# output_cpld.net
KiCad netlist of a schematic drawn in EAGLE
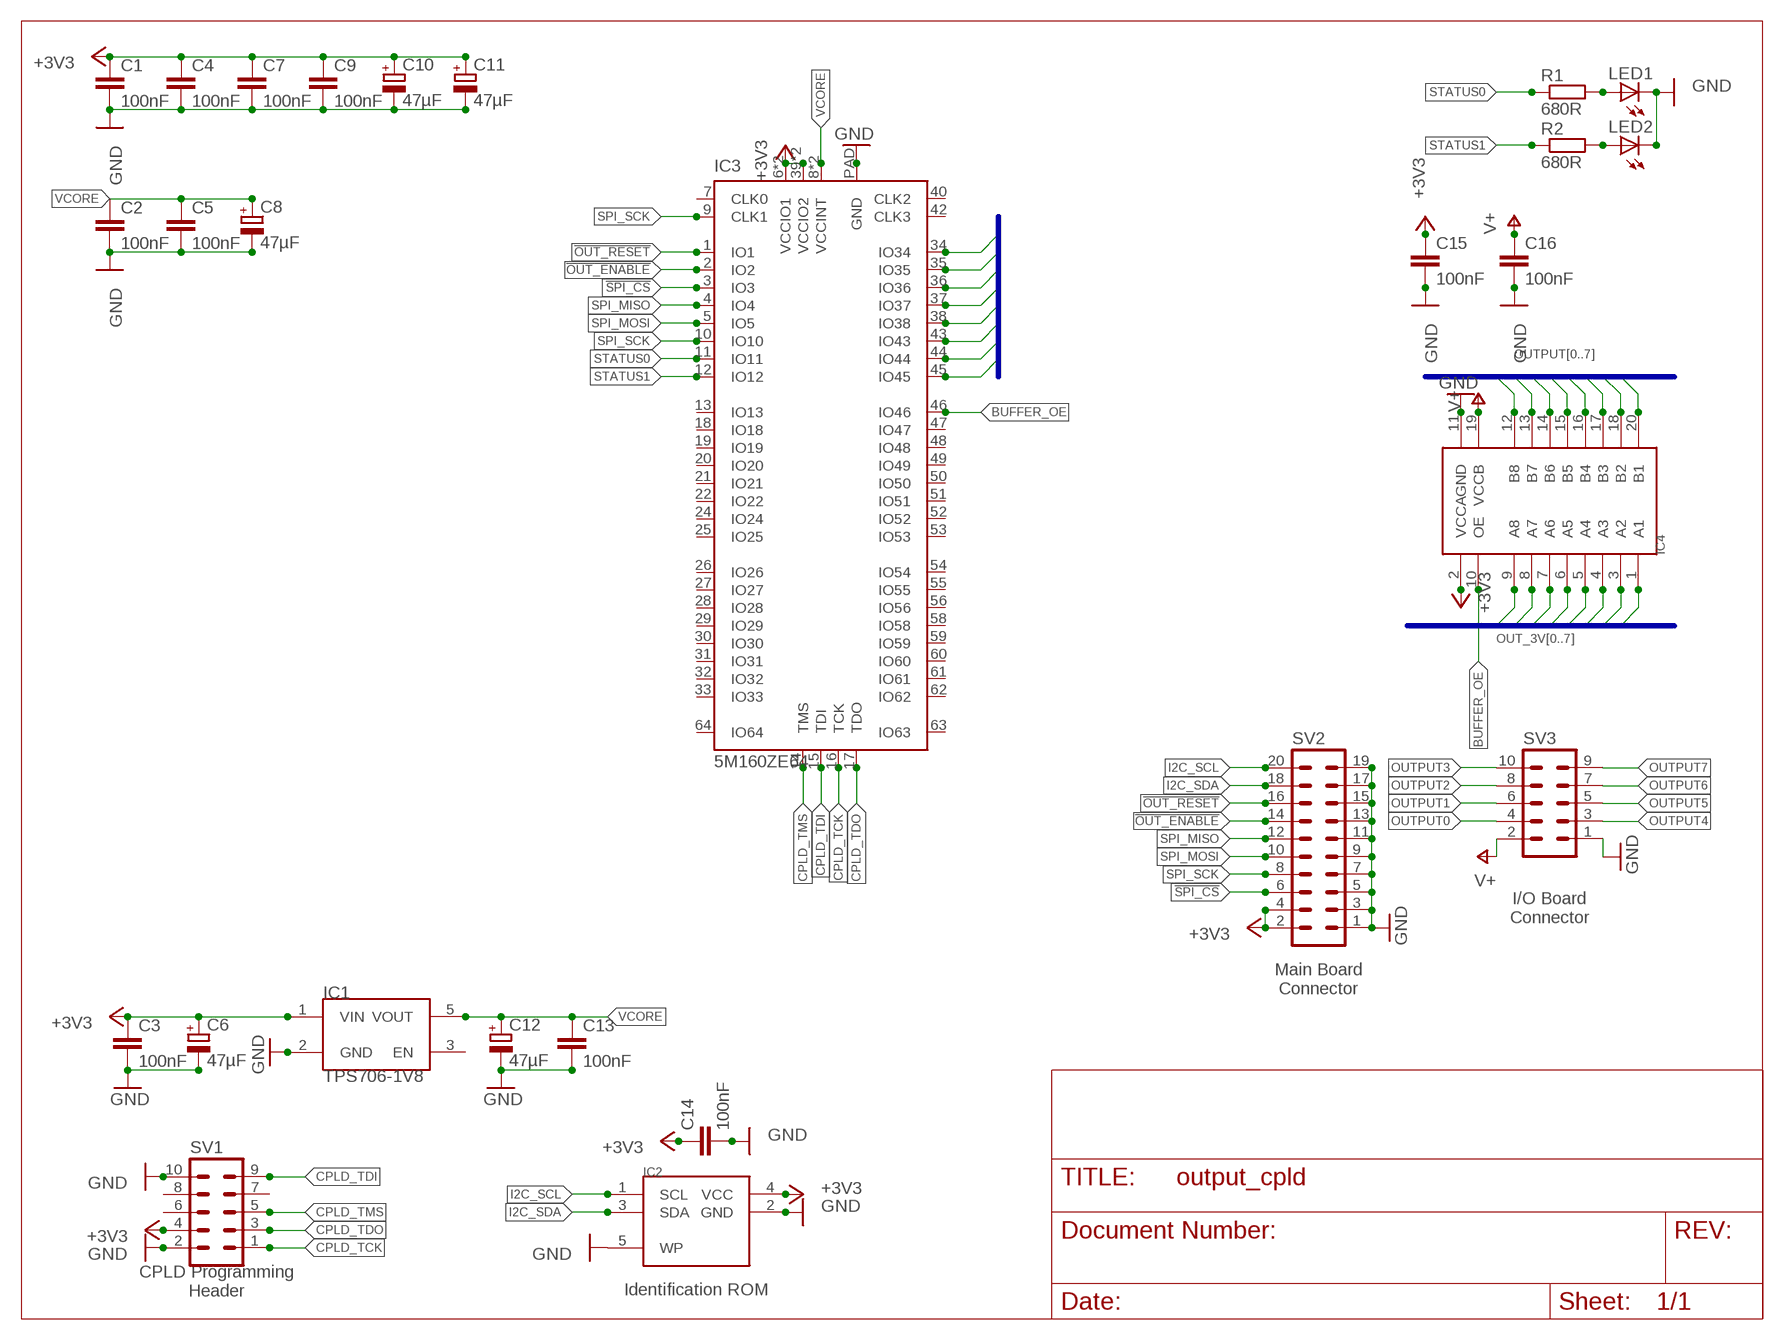
[diagram p0: schematic, sheet 1]

(export (version "E")
  (design (tool "Eeschema 10.0.6"))
  (components
    (comp (ref "C1")
      (value "100nF")
      (footprint "eagle-import:C0805")
      (libsource (lib "eagle-import") (part "C-EUC0805"))
    )
    (comp (ref "C2")
      (value "100nF")
      (footprint "eagle-import:C0805")
      (libsource (lib "eagle-import") (part "C-EUC0805"))
    )
    (comp (ref "C3")
      (value "100nF")
      (footprint "eagle-import:C0805")
      (libsource (lib "eagle-import") (part "C-EUC0805"))
    )
    (comp (ref "C4")
      (value "100nF")
      (footprint "eagle-import:C0805")
      (libsource (lib "eagle-import") (part "C-EUC0805"))
    )
    (comp (ref "C5")
      (value "100nF")
      (footprint "eagle-import:C0805")
      (libsource (lib "eagle-import") (part "C-EUC0805"))
    )
    (comp (ref "C6")
      (value "47µF")
      (footprint "eagle-import:CT6032")
      (libsource (lib "eagle-import") (part "CPOL-EUCT6032"))
    )
    (comp (ref "C7")
      (value "100nF")
      (footprint "eagle-import:C0805")
      (libsource (lib "eagle-import") (part "C-EUC0805"))
    )
    (comp (ref "C8")
      (value "47µF")
      (footprint "eagle-import:CT6032")
      (libsource (lib "eagle-import") (part "CPOL-EUCT6032"))
    )
    (comp (ref "C9")
      (value "100nF")
      (footprint "eagle-import:C0805")
      (libsource (lib "eagle-import") (part "C-EUC0805"))
    )
    (comp (ref "C10")
      (value "47µF")
      (footprint "eagle-import:CT6032")
      (libsource (lib "eagle-import") (part "CPOL-EUCT6032"))
    )
    (comp (ref "C11")
      (value "47µF")
      (footprint "eagle-import:CT6032")
      (libsource (lib "eagle-import") (part "CPOL-EUCT6032"))
    )
    (comp (ref "C12")
      (value "47µF")
      (footprint "eagle-import:CT6032")
      (libsource (lib "eagle-import") (part "CPOL-EUCT6032"))
    )
    (comp (ref "C13")
      (value "100nF")
      (footprint "eagle-import:C0805")
      (libsource (lib "eagle-import") (part "C-EUC0805"))
    )
    (comp (ref "C14")
      (value "100nF")
      (footprint "eagle-import:C0805")
      (libsource (lib "eagle-import") (part "C-EUC0805"))
    )
    (comp (ref "C15")
      (value "100nF")
      (footprint "eagle-import:C0805")
      (libsource (lib "eagle-import") (part "C-EUC0805"))
    )
    (comp (ref "C16")
      (value "100nF")
      (footprint "eagle-import:C0805")
      (libsource (lib "eagle-import") (part "C-EUC0805"))
    )
    (comp (ref "IC1")
      (value "TPS706-1V8")
      (footprint "eagle-import:SOT23-5")
      (libsource (lib "eagle-import") (part "TPS706SOT23-5"))
    )
    (comp (ref "IC2")
      (value "AT24C02D")
      (footprint "eagle-import:SOT23-5")
      (libsource (lib "eagle-import") (part "AT24C02D"))
    )
    (comp (ref "IC3")
      (value "5M160ZE64")
      (footprint "eagle-import:EQFP64")
      (libsource (lib "eagle-import") (part "5M160ZE64"))
    )
    (comp (ref "IC4")
      (value "TXB0108TSSOP20")
      (footprint "eagle-import:TSSOP20")
      (libsource (lib "eagle-import") (part "TXB0108TSSOP20"))
    )
    (comp (ref "LED1")
      (value "LEDCHIPLED_1206")
      (footprint "eagle-import:CHIPLED_1206")
      (libsource (lib "eagle-import") (part "LEDCHIPLED_1206"))
    )
    (comp (ref "LED2")
      (value "LEDCHIPLED_1206")
      (footprint "eagle-import:CHIPLED_1206")
      (libsource (lib "eagle-import") (part "LEDCHIPLED_1206"))
    )
    (comp (ref "R1")
      (value "680R")
      (footprint "eagle-import:M0805")
      (libsource (lib "eagle-import") (part "R-EU_M0805"))
    )
    (comp (ref "R2")
      (value "680R")
      (footprint "eagle-import:M0805")
      (libsource (lib "eagle-import") (part "R-EU_M0805"))
    )
    (comp (ref "SV1")
      (value "MA05-2")
      (footprint "eagle-import:MA05-2")
      (libsource (lib "eagle-import") (part "MA05-2"))
    )
    (comp (ref "SV2")
      (value "MA10-2")
      (footprint "eagle-import:MA10-2")
      (libsource (lib "eagle-import") (part "MA10-2"))
    )
    (comp (ref "SV3")
      (value "MA05-2")
      (footprint "eagle-import:MA05-2")
      (libsource (lib "eagle-import") (part "MA05-2"))
    )
  )
  (nets
    (net (code "1") (name "+3V3") (class "Default")
      (node (ref "C1") (pin "1") (pinfunction "1_1") (pintype "passive"))
      (node (ref "C10") (pin "+") (pinfunction "+_+") (pintype "passive"))
      (node (ref "C11") (pin "+") (pinfunction "+_+") (pintype "passive"))
      (node (ref "C14") (pin "1") (pinfunction "1_1") (pintype "passive"))
      (node (ref "C15") (pin "1") (pinfunction "1_1") (pintype "passive"))
      (node (ref "C3") (pin "1") (pinfunction "1_1") (pintype "passive"))
      (node (ref "C4") (pin "1") (pinfunction "1_1") (pintype "passive"))
      (node (ref "C6") (pin "+") (pinfunction "+_+") (pintype "passive"))
      (node (ref "C7") (pin "1") (pinfunction "1_1") (pintype "passive"))
      (node (ref "C9") (pin "1") (pinfunction "1_1") (pintype "passive"))
      (node (ref "IC1") (pin "1") (pinfunction "VIN_1") (pintype "bidirectional"))
      (node (ref "IC2") (pin "4") (pinfunction "VCC_4") (pintype "power_in"))
      (node (ref "IC3") (pin "23") (pinfunction "VCCIO1_23") (pintype "power_in"))
      (node (ref "IC3") (pin "39") (pinfunction "VCCIO2_39") (pintype "power_in"))
      (node (ref "IC3") (pin "57") (pinfunction "VCCIO2_57") (pintype "power_in"))
      (node (ref "IC3") (pin "6") (pinfunction "VCCIO1_6") (pintype "power_in"))
      (node (ref "IC4") (pin "2") (pinfunction "VCCA_2") (pintype "bidirectional"))
      (node (ref "SV1") (pin "4") (pinfunction "4_4") (pintype "passive"))
      (node (ref "SV2") (pin "2") (pinfunction "2_2") (pintype "passive"))
      (node (ref "SV2") (pin "4") (pinfunction "4_4") (pintype "passive"))
    )
    (net (code "3") (name "/OUT_3V0") (class "Default")
      (node (ref "IC3") (pin "34") (pinfunction "IO34_34") (pintype "bidirectional"))
      (node (ref "IC4") (pin "1") (pinfunction "A1_1") (pintype "bidirectional"))
    )
    (net (code "4") (name "/OUT_3V1") (class "Default")
      (node (ref "IC3") (pin "35") (pinfunction "IO35_35") (pintype "bidirectional"))
      (node (ref "IC4") (pin "3") (pinfunction "A2_3") (pintype "bidirectional"))
    )
    (net (code "5") (name "/OUT_3V2") (class "Default")
      (node (ref "IC3") (pin "36") (pinfunction "IO36_36") (pintype "bidirectional"))
      (node (ref "IC4") (pin "4") (pinfunction "A3_4") (pintype "bidirectional"))
    )
    (net (code "6") (name "/OUT_3V3") (class "Default")
      (node (ref "IC3") (pin "37") (pinfunction "IO37_37") (pintype "bidirectional"))
      (node (ref "IC4") (pin "5") (pinfunction "A4_5") (pintype "bidirectional"))
    )
    (net (code "7") (name "/OUT_3V4") (class "Default")
      (node (ref "IC3") (pin "38") (pinfunction "IO38_38") (pintype "bidirectional"))
      (node (ref "IC4") (pin "6") (pinfunction "A5_6") (pintype "bidirectional"))
    )
    (net (code "8") (name "/OUT_3V5") (class "Default")
      (node (ref "IC3") (pin "43") (pinfunction "IO43_43") (pintype "bidirectional"))
      (node (ref "IC4") (pin "7") (pinfunction "A6_7") (pintype "bidirectional"))
    )
    (net (code "9") (name "/OUT_3V6") (class "Default")
      (node (ref "IC3") (pin "44") (pinfunction "IO44_44") (pintype "bidirectional"))
      (node (ref "IC4") (pin "8") (pinfunction "A7_8") (pintype "bidirectional"))
    )
    (net (code "10") (name "/OUT_3V7") (class "Default")
      (node (ref "IC3") (pin "45") (pinfunction "IO45_45") (pintype "bidirectional"))
      (node (ref "IC4") (pin "9") (pinfunction "A8_9") (pintype "bidirectional"))
    )
    (net (code "12") (name "/~{OUT_ENABLE}") (class "Default")
      (node (ref "IC3") (pin "2") (pinfunction "IO2_2") (pintype "bidirectional"))
      (node (ref "SV2") (pin "14") (pinfunction "14_14") (pintype "passive"))
    )
    (net (code "13") (name "/~{OUT_RESET}") (class "Default")
      (node (ref "IC3") (pin "1") (pinfunction "IO1_1") (pintype "bidirectional"))
      (node (ref "SV2") (pin "16") (pinfunction "16_16") (pintype "passive"))
    )
    (net (code "14") (name "/~{SPI_CS}") (class "Default")
      (node (ref "IC3") (pin "3") (pinfunction "IO3_3") (pintype "bidirectional"))
      (node (ref "SV2") (pin "6") (pinfunction "6_6") (pintype "passive"))
    )
    (net (code "15") (name "BUFFER_OE") (class "Default")
      (node (ref "IC3") (pin "46") (pinfunction "IO46_46") (pintype "bidirectional"))
      (node (ref "IC4") (pin "10") (pinfunction "OE_10") (pintype "bidirectional"))
    )
    (net (code "16") (name "CPLD_TCK") (class "Default")
      (node (ref "IC3") (pin "16") (pinfunction "TCK_16") (pintype "input"))
      (node (ref "SV1") (pin "1") (pinfunction "1_1") (pintype "passive"))
    )
    (net (code "17") (name "CPLD_TDI") (class "Default")
      (node (ref "IC3") (pin "15") (pinfunction "TDI_15") (pintype "input"))
      (node (ref "SV1") (pin "9") (pinfunction "9_9") (pintype "passive"))
    )
    (net (code "18") (name "CPLD_TDO") (class "Default")
      (node (ref "IC3") (pin "17") (pinfunction "TDO_17") (pintype "output"))
      (node (ref "SV1") (pin "3") (pinfunction "3_3") (pintype "passive"))
    )
    (net (code "19") (name "CPLD_TMS") (class "Default")
      (node (ref "IC3") (pin "14") (pinfunction "TMS_14") (pintype "input"))
      (node (ref "SV1") (pin "5") (pinfunction "5_5") (pintype "passive"))
    )
    (net (code "20") (name "GND") (class "Default")
      (node (ref "C1") (pin "2") (pinfunction "2_2") (pintype "passive"))
      (node (ref "C10") (pin "-") (pinfunction "-_-") (pintype "passive"))
      (node (ref "C11") (pin "-") (pinfunction "-_-") (pintype "passive"))
      (node (ref "C12") (pin "-") (pinfunction "-_-") (pintype "passive"))
      (node (ref "C13") (pin "2") (pinfunction "2_2") (pintype "passive"))
      (node (ref "C14") (pin "2") (pinfunction "2_2") (pintype "passive"))
      (node (ref "C15") (pin "2") (pinfunction "2_2") (pintype "passive"))
      (node (ref "C16") (pin "2") (pinfunction "2_2") (pintype "passive"))
      (node (ref "C2") (pin "2") (pinfunction "2_2") (pintype "passive"))
      (node (ref "C3") (pin "2") (pinfunction "2_2") (pintype "passive"))
      (node (ref "C4") (pin "2") (pinfunction "2_2") (pintype "passive"))
      (node (ref "C5") (pin "2") (pinfunction "2_2") (pintype "passive"))
      (node (ref "C6") (pin "-") (pinfunction "-_-") (pintype "passive"))
      (node (ref "C7") (pin "2") (pinfunction "2_2") (pintype "passive"))
      (node (ref "C8") (pin "-") (pinfunction "-_-") (pintype "passive"))
      (node (ref "C9") (pin "2") (pinfunction "2_2") (pintype "passive"))
      (node (ref "IC1") (pin "2") (pinfunction "GND_2") (pintype "bidirectional"))
      (node (ref "IC2") (pin "2") (pinfunction "GND_2") (pintype "power_in"))
      (node (ref "IC2") (pin "5") (pinfunction "WP_5") (pintype "bidirectional"))
      (node (ref "IC3") (pin "PAD") (pinfunction "GND_PAD") (pintype "power_in"))
      (node (ref "IC4") (pin "11") (pinfunction "GND_11") (pintype "bidirectional"))
      (node (ref "LED1") (pin "C") (pinfunction "C_C") (pintype "passive"))
      (node (ref "LED2") (pin "C") (pinfunction "C_C") (pintype "passive"))
      (node (ref "SV1") (pin "10") (pinfunction "10_10") (pintype "passive"))
      (node (ref "SV1") (pin "2") (pinfunction "2_2") (pintype "passive"))
      (node (ref "SV2") (pin "1") (pinfunction "1_1") (pintype "passive"))
      (node (ref "SV2") (pin "11") (pinfunction "11_11") (pintype "passive"))
      (node (ref "SV2") (pin "13") (pinfunction "13_13") (pintype "passive"))
      (node (ref "SV2") (pin "15") (pinfunction "15_15") (pintype "passive"))
      (node (ref "SV2") (pin "17") (pinfunction "17_17") (pintype "passive"))
      (node (ref "SV2") (pin "19") (pinfunction "19_19") (pintype "passive"))
      (node (ref "SV2") (pin "3") (pinfunction "3_3") (pintype "passive"))
      (node (ref "SV2") (pin "5") (pinfunction "5_5") (pintype "passive"))
      (node (ref "SV2") (pin "7") (pinfunction "7_7") (pintype "passive"))
      (node (ref "SV2") (pin "9") (pinfunction "9_9") (pintype "passive"))
      (node (ref "SV3") (pin "1") (pinfunction "1_1") (pintype "passive"))
    )
    (net (code "21") (name "I2C_SCL") (class "Default")
      (node (ref "IC2") (pin "1") (pinfunction "SCL_1") (pintype "bidirectional"))
      (node (ref "SV2") (pin "20") (pinfunction "20_20") (pintype "passive"))
    )
    (net (code "22") (name "I2C_SDA") (class "Default")
      (node (ref "IC2") (pin "3") (pinfunction "SDA_3") (pintype "bidirectional"))
      (node (ref "SV2") (pin "18") (pinfunction "18_18") (pintype "passive"))
    )
    (net (code "23") (name "Net-(LED1-PadA)") (class "Default")
      (node (ref "LED1") (pin "A") (pinfunction "A_A") (pintype "passive"))
      (node (ref "R1") (pin "2") (pinfunction "2_2") (pintype "passive"))
    )
    (net (code "24") (name "Net-(LED2-PadA)") (class "Default")
      (node (ref "LED2") (pin "A") (pinfunction "A_A") (pintype "passive"))
      (node (ref "R2") (pin "2") (pinfunction "2_2") (pintype "passive"))
    )
    (net (code "25") (name "OUTPUT0") (class "Default")
      (node (ref "IC4") (pin "20") (pinfunction "B1_20") (pintype "bidirectional"))
      (node (ref "SV3") (pin "4") (pinfunction "4_4") (pintype "passive"))
    )
    (net (code "26") (name "OUTPUT1") (class "Default")
      (node (ref "IC4") (pin "18") (pinfunction "B2_18") (pintype "bidirectional"))
      (node (ref "SV3") (pin "6") (pinfunction "6_6") (pintype "passive"))
    )
    (net (code "27") (name "OUTPUT2") (class "Default")
      (node (ref "IC4") (pin "17") (pinfunction "B3_17") (pintype "bidirectional"))
      (node (ref "SV3") (pin "8") (pinfunction "8_8") (pintype "passive"))
    )
    (net (code "28") (name "OUTPUT3") (class "Default")
      (node (ref "IC4") (pin "16") (pinfunction "B4_16") (pintype "bidirectional"))
      (node (ref "SV3") (pin "10") (pinfunction "10_10") (pintype "passive"))
    )
    (net (code "29") (name "OUTPUT4") (class "Default")
      (node (ref "IC4") (pin "15") (pinfunction "B5_15") (pintype "bidirectional"))
      (node (ref "SV3") (pin "3") (pinfunction "3_3") (pintype "passive"))
    )
    (net (code "30") (name "OUTPUT5") (class "Default")
      (node (ref "IC4") (pin "14") (pinfunction "B6_14") (pintype "bidirectional"))
      (node (ref "SV3") (pin "5") (pinfunction "5_5") (pintype "passive"))
    )
    (net (code "31") (name "OUTPUT6") (class "Default")
      (node (ref "IC4") (pin "13") (pinfunction "B7_13") (pintype "bidirectional"))
      (node (ref "SV3") (pin "7") (pinfunction "7_7") (pintype "passive"))
    )
    (net (code "32") (name "OUTPUT7") (class "Default")
      (node (ref "IC4") (pin "12") (pinfunction "B8_12") (pintype "bidirectional"))
      (node (ref "SV3") (pin "9") (pinfunction "9_9") (pintype "passive"))
    )
    (net (code "33") (name "SPI_MISO") (class "Default")
      (node (ref "IC3") (pin "4") (pinfunction "IO4_4") (pintype "bidirectional"))
      (node (ref "SV2") (pin "12") (pinfunction "12_12") (pintype "passive"))
    )
    (net (code "34") (name "SPI_MOSI") (class "Default")
      (node (ref "IC3") (pin "5") (pinfunction "IO5_5") (pintype "bidirectional"))
      (node (ref "SV2") (pin "10") (pinfunction "10_10") (pintype "passive"))
    )
    (net (code "35") (name "SPI_SCK") (class "Default")
      (node (ref "IC3") (pin "10") (pinfunction "IO10_10") (pintype "bidirectional"))
      (node (ref "IC3") (pin "9") (pinfunction "CLK1_9") (pintype "bidirectional"))
      (node (ref "SV2") (pin "8") (pinfunction "8_8") (pintype "passive"))
    )
    (net (code "36") (name "STATUS0") (class "Default")
      (node (ref "IC3") (pin "11") (pinfunction "IO11_11") (pintype "bidirectional"))
      (node (ref "R1") (pin "1") (pinfunction "1_1") (pintype "passive"))
    )
    (net (code "37") (name "STATUS1") (class "Default")
      (node (ref "IC3") (pin "12") (pinfunction "IO12_12") (pintype "bidirectional"))
      (node (ref "R2") (pin "1") (pinfunction "1_1") (pintype "passive"))
    )
    (net (code "38") (name "V+") (class "Default")
      (node (ref "C16") (pin "1") (pinfunction "1_1") (pintype "passive"))
      (node (ref "IC4") (pin "19") (pinfunction "VCCB_19") (pintype "bidirectional"))
      (node (ref "SV3") (pin "2") (pinfunction "2_2") (pintype "passive"))
    )
    (net (code "39") (name "VCORE") (class "Default")
      (node (ref "C12") (pin "+") (pinfunction "+_+") (pintype "passive"))
      (node (ref "C13") (pin "1") (pinfunction "1_1") (pintype "passive"))
      (node (ref "C2") (pin "1") (pinfunction "1_1") (pintype "passive"))
      (node (ref "C5") (pin "1") (pinfunction "1_1") (pintype "passive"))
      (node (ref "C8") (pin "+") (pinfunction "+_+") (pintype "passive"))
      (node (ref "IC1") (pin "5") (pinfunction "VOUT_5") (pintype "bidirectional"))
      (node (ref "IC3") (pin "41") (pinfunction "VCCINT_41") (pintype "power_in"))
      (node (ref "IC3") (pin "8") (pinfunction "VCCINT_8") (pintype "power_in"))
    )
    (net (code "40") (name "unconnected-(IC1-EN-Pad3)") (class "Default")
      (node (ref "IC1") (pin "3") (pinfunction "EN_3") (pintype "bidirectional"))
    )
    (net (code "41") (name "unconnected-(IC3-CLK0-Pad7)") (class "Default")
      (node (ref "IC3") (pin "7") (pinfunction "CLK0_7") (pintype "bidirectional"))
    )
    (net (code "42") (name "unconnected-(IC3-CLK2-Pad40)") (class "Default")
      (node (ref "IC3") (pin "40") (pinfunction "CLK2_40") (pintype "bidirectional"))
    )
    (net (code "43") (name "unconnected-(IC3-CLK3-Pad42)") (class "Default")
      (node (ref "IC3") (pin "42") (pinfunction "CLK3_42") (pintype "bidirectional"))
    )
    (net (code "44") (name "unconnected-(IC3-IO13-Pad13)") (class "Default")
      (node (ref "IC3") (pin "13") (pinfunction "IO13_13") (pintype "bidirectional"))
    )
    (net (code "45") (name "unconnected-(IC3-IO18-Pad18)") (class "Default")
      (node (ref "IC3") (pin "18") (pinfunction "IO18_18") (pintype "bidirectional"))
    )
    (net (code "46") (name "unconnected-(IC3-IO19-Pad19)") (class "Default")
      (node (ref "IC3") (pin "19") (pinfunction "IO19_19") (pintype "bidirectional"))
    )
    (net (code "47") (name "unconnected-(IC3-IO20-Pad20)") (class "Default")
      (node (ref "IC3") (pin "20") (pinfunction "IO20_20") (pintype "bidirectional"))
    )
    (net (code "48") (name "unconnected-(IC3-IO21-Pad21)") (class "Default")
      (node (ref "IC3") (pin "21") (pinfunction "IO21_21") (pintype "bidirectional"))
    )
    (net (code "49") (name "unconnected-(IC3-IO22-Pad22)") (class "Default")
      (node (ref "IC3") (pin "22") (pinfunction "IO22_22") (pintype "bidirectional"))
    )
    (net (code "50") (name "unconnected-(IC3-IO24-Pad24)") (class "Default")
      (node (ref "IC3") (pin "24") (pinfunction "IO24_24") (pintype "bidirectional"))
    )
    (net (code "51") (name "unconnected-(IC3-IO25-Pad25)") (class "Default")
      (node (ref "IC3") (pin "25") (pinfunction "IO25_25") (pintype "bidirectional"))
    )
    (net (code "52") (name "unconnected-(IC3-IO26-Pad26)") (class "Default")
      (node (ref "IC3") (pin "26") (pinfunction "IO26_26") (pintype "bidirectional"))
    )
    (net (code "53") (name "unconnected-(IC3-IO27-Pad27)") (class "Default")
      (node (ref "IC3") (pin "27") (pinfunction "IO27_27") (pintype "bidirectional"))
    )
    (net (code "54") (name "unconnected-(IC3-IO28-Pad28)") (class "Default")
      (node (ref "IC3") (pin "28") (pinfunction "IO28_28") (pintype "bidirectional"))
    )
    (net (code "55") (name "unconnected-(IC3-IO29-Pad29)") (class "Default")
      (node (ref "IC3") (pin "29") (pinfunction "IO29_29") (pintype "bidirectional"))
    )
    (net (code "56") (name "unconnected-(IC3-IO30-Pad30)") (class "Default")
      (node (ref "IC3") (pin "30") (pinfunction "IO30_30") (pintype "bidirectional"))
    )
    (net (code "57") (name "unconnected-(IC3-IO31-Pad31)") (class "Default")
      (node (ref "IC3") (pin "31") (pinfunction "IO31_31") (pintype "bidirectional"))
    )
    (net (code "58") (name "unconnected-(IC3-IO32-Pad32)") (class "Default")
      (node (ref "IC3") (pin "32") (pinfunction "IO32_32") (pintype "bidirectional"))
    )
    (net (code "59") (name "unconnected-(IC3-IO33-Pad33)") (class "Default")
      (node (ref "IC3") (pin "33") (pinfunction "IO33_33") (pintype "bidirectional"))
    )
    (net (code "60") (name "unconnected-(IC3-IO47-Pad47)") (class "Default")
      (node (ref "IC3") (pin "47") (pinfunction "IO47_47") (pintype "bidirectional"))
    )
    (net (code "61") (name "unconnected-(IC3-IO48-Pad48)") (class "Default")
      (node (ref "IC3") (pin "48") (pinfunction "IO48_48") (pintype "bidirectional"))
    )
    (net (code "62") (name "unconnected-(IC3-IO49-Pad49)") (class "Default")
      (node (ref "IC3") (pin "49") (pinfunction "IO49_49") (pintype "bidirectional"))
    )
    (net (code "63") (name "unconnected-(IC3-IO50-Pad50)") (class "Default")
      (node (ref "IC3") (pin "50") (pinfunction "IO50_50") (pintype "bidirectional"))
    )
    (net (code "64") (name "unconnected-(IC3-IO51-Pad51)") (class "Default")
      (node (ref "IC3") (pin "51") (pinfunction "IO51_51") (pintype "bidirectional"))
    )
    (net (code "65") (name "unconnected-(IC3-IO52-Pad52)") (class "Default")
      (node (ref "IC3") (pin "52") (pinfunction "IO52_52") (pintype "bidirectional"))
    )
    (net (code "66") (name "unconnected-(IC3-IO53-Pad53)") (class "Default")
      (node (ref "IC3") (pin "53") (pinfunction "IO53_53") (pintype "bidirectional"))
    )
    (net (code "67") (name "unconnected-(IC3-IO54-Pad54)") (class "Default")
      (node (ref "IC3") (pin "54") (pinfunction "IO54_54") (pintype "bidirectional"))
    )
    (net (code "68") (name "unconnected-(IC3-IO55-Pad55)") (class "Default")
      (node (ref "IC3") (pin "55") (pinfunction "IO55_55") (pintype "bidirectional"))
    )
    (net (code "69") (name "unconnected-(IC3-IO56-Pad56)") (class "Default")
      (node (ref "IC3") (pin "56") (pinfunction "IO56_56") (pintype "bidirectional"))
    )
    (net (code "70") (name "unconnected-(IC3-IO58-Pad58)") (class "Default")
      (node (ref "IC3") (pin "58") (pinfunction "IO58_58") (pintype "bidirectional"))
    )
    (net (code "71") (name "unconnected-(IC3-IO59-Pad59)") (class "Default")
      (node (ref "IC3") (pin "59") (pinfunction "IO59_59") (pintype "bidirectional"))
    )
    (net (code "72") (name "unconnected-(IC3-IO60-Pad60)") (class "Default")
      (node (ref "IC3") (pin "60") (pinfunction "IO60_60") (pintype "bidirectional"))
    )
    (net (code "73") (name "unconnected-(IC3-IO61-Pad61)") (class "Default")
      (node (ref "IC3") (pin "61") (pinfunction "IO61_61") (pintype "bidirectional"))
    )
    (net (code "74") (name "unconnected-(IC3-IO62-Pad62)") (class "Default")
      (node (ref "IC3") (pin "62") (pinfunction "IO62_62") (pintype "bidirectional"))
    )
    (net (code "75") (name "unconnected-(IC3-IO63-Pad63)") (class "Default")
      (node (ref "IC3") (pin "63") (pinfunction "IO63_63") (pintype "bidirectional"))
    )
    (net (code "76") (name "unconnected-(IC3-IO64-Pad64)") (class "Default")
      (node (ref "IC3") (pin "64") (pinfunction "IO64_64") (pintype "bidirectional"))
    )
    (net (code "77") (name "unconnected-(SV1-Pad6)") (class "Default")
      (node (ref "SV1") (pin "6") (pinfunction "6_6") (pintype "passive"))
    )
    (net (code "78") (name "unconnected-(SV1-Pad7)") (class "Default")
      (node (ref "SV1") (pin "7") (pinfunction "7_7") (pintype "passive"))
    )
    (net (code "79") (name "unconnected-(SV1-Pad8)") (class "Default")
      (node (ref "SV1") (pin "8") (pinfunction "8_8") (pintype "passive"))
    )
  )
)
